# USB-NORA-W1_SCHEM_03.net
KiCad netlist of a schematic drawn in Altium Designer
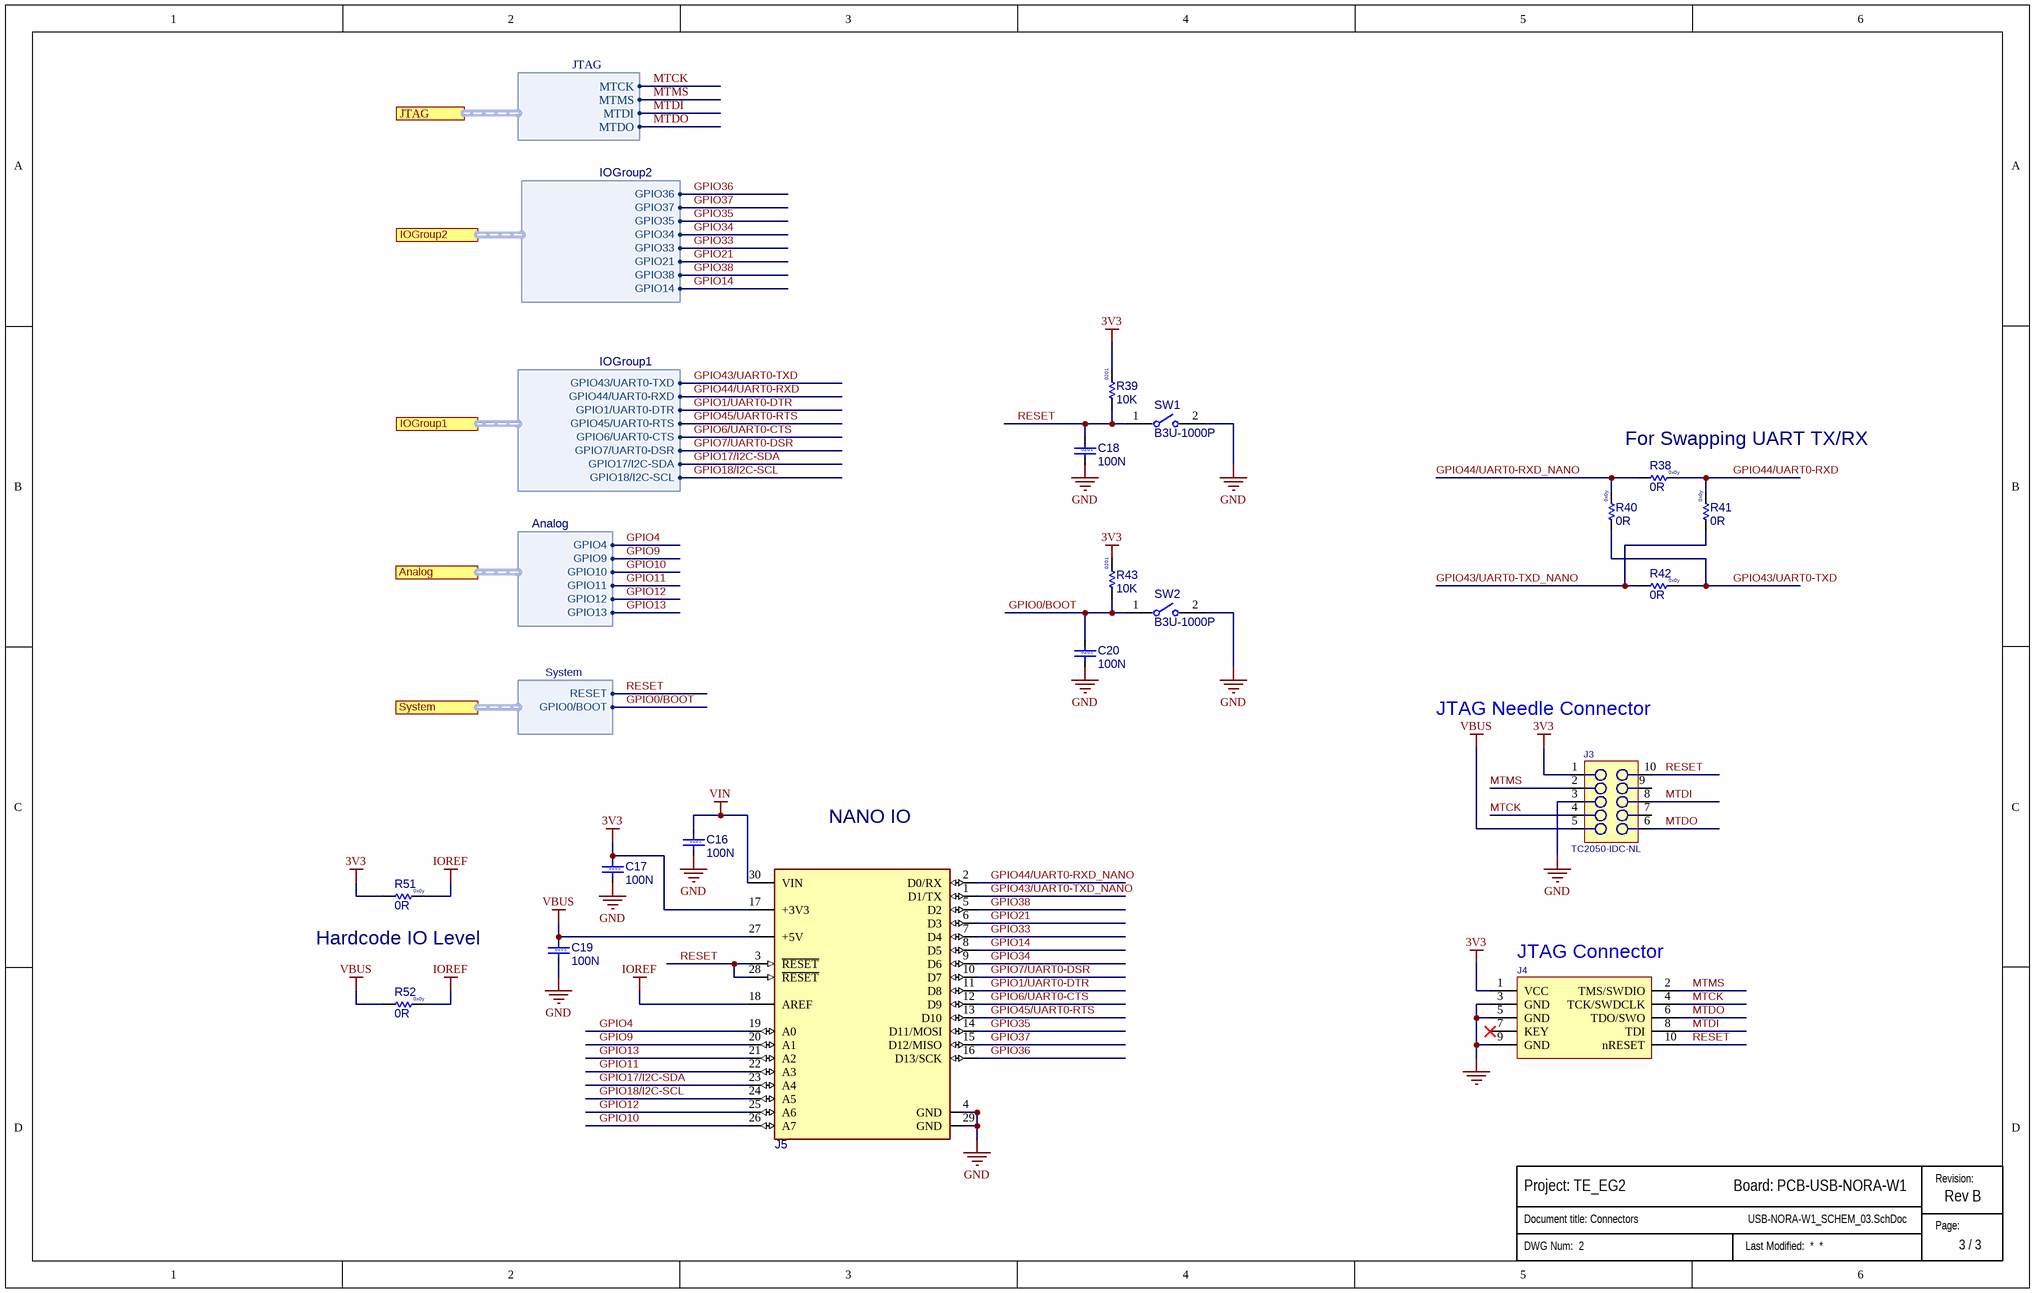
[diagram p0: USB-NORA-W1_SCHEM_03.SchDoc]

(export (version "E")
  (design (tool "Eeschema 10.0.6"))
  (components
    (comp (ref "C16")
      (value "100N")
      (footprint "Cap 0201 HD")
      (description "CAP CER X5R 0201 100N 10% 10V")
      (fields
        (field (name "SIZE") "0201")
        (field (name "PART NUMBER") "UBXH01-0000245")
        (field (name "TOLERANCE") "10%")
        (field (name "EDITOR") "dario.antonaz")
        (field (name "RELEASED BY") "jure.podmenik")
      )
      (libsource (lib "UBX_Parts_DB_Lib") (part "Cap Chip"))
    )
    (comp (ref "C17")
      (value "100N")
      (footprint "Cap 0201 HD")
      (description "CAP CER X5R 0201 100N 10% 10V")
      (fields
        (field (name "SIZE") "0201")
        (field (name "PART NUMBER") "UBXH01-0000245")
        (field (name "TOLERANCE") "10%")
        (field (name "EDITOR") "dario.antonaz")
        (field (name "RELEASED BY") "jure.podmenik")
      )
      (libsource (lib "UBX_Parts_DB_Lib") (part "Cap Chip"))
    )
    (comp (ref "C18")
      (value "100N")
      (footprint "Cap 0201 HD")
      (description "CAP CER X5R 0201 100N 10% 10V")
      (fields
        (field (name "SIZE") "0201")
        (field (name "PART NUMBER") "UBXH01-0000245")
        (field (name "TOLERANCE") "10%")
        (field (name "EDITOR") "dario.antonaz")
        (field (name "RELEASED BY") "jure.podmenik")
      )
      (libsource (lib "UBX_Parts_DB_Lib") (part "Cap Chip"))
    )
    (comp (ref "C19")
      (value "100N")
      (footprint "Cap 0201 HD")
      (description "CAP CER X5R 0201 100N 10% 10V")
      (fields
        (field (name "SIZE") "0201")
        (field (name "PART NUMBER") "UBXH01-0000245")
        (field (name "TOLERANCE") "10%")
        (field (name "EDITOR") "dario.antonaz")
        (field (name "RELEASED BY") "jure.podmenik")
      )
      (libsource (lib "UBX_Parts_DB_Lib") (part "Cap Chip"))
    )
    (comp (ref "C20")
      (value "100N")
      (footprint "Cap 0201 HD")
      (description "CAP CER X5R 0201 100N 10% 10V")
      (fields
        (field (name "SIZE") "0201")
        (field (name "PART NUMBER") "UBXH01-0000245")
        (field (name "TOLERANCE") "10%")
        (field (name "EDITOR") "dario.antonaz")
        (field (name "RELEASED BY") "jure.podmenik")
      )
      (libsource (lib "UBX_Parts_DB_Lib") (part "Cap Chip"))
    )
    (comp (ref "J3")
      (value "TC2050-IDC-NLDNP")
      (footprint "TC2050-IDC-NL")
      (description "CON PADS FOR CBL PLUG-OF-NAILS 10-PIN NO LEGS")
      (fields
        (field (name "MANUFACTURER P/N") "TC2050-IDC-NL")
        (field (name "PART NUMBER") "TC2050-IDC-NL")
        (field (name "MANUFACTURER") "TAG Connect")
        (field (name "ADDED BY") "Paul B")
      )
      (libsource (lib "LEGACY_Rigado_AltiumLib") (part "CON-10Pin_2Row_ALT"))
    )
    (comp (ref "J4")
      (value "130-00099")
      (footprint "HDR.050P-10Pin-2x5-SMT_Key")
      (description "Header 0.05\" 10Pin 2Row SMD Black")
      (fields (field (name "MANUFACTURER") "Samtec"))
      (libsource (lib "Arena_Parts_DB_Lib") (part "JTAG-10Pin"))
    )
    (comp (ref "J5")
      (value "UNK_Arduino")
      (footprint "UNK_Arduino")
      (description "ARDUINO NANO 33 IOT CONN")
      (fields (field (name "PART NUMBER") "UBXH04-0000717") (field (name "EDITOR") "aneeb.sohail"))
      (libsource (lib "UBX_Parts_DB_Lib") (part "UNK_Arduino"))
    )
    (comp (ref "R38")
      (value "0R")
      (footprint "RES 0402 HD")
      (description "RES THICK FILM CHIP 0402")
      (fields
        (field (name "SIZE") "0x0y")
        (field (name "PART NUMBER") "UBXH18-0003002")
        (field (name "TOLERANCE") "0")
        (field (name "EDITOR") "charlotte.biber")
        (field (name "RELEASED BY") "peter.mueller")
      )
      (libsource (lib "UBX_Parts_DB_Lib") (part "Res sm"))
    )
    (comp (ref "R39")
      (value "10K")
      (footprint "RES 0201 HD")
      (description "RES THICK FILM CHIP 0201 10K 5% 50mW")
      (fields
        (field (name "SIZE") "0201")
        (field (name "PART NUMBER") "UBXH18-0001097")
        (field (name "TOLERANCE") "5%")
        (field (name "EDITOR") "martin.pilik")
        (field (name "RELEASED BY") "fabrice.bret-dibat")
      )
      (libsource (lib "UBX_Parts_DB_Lib") (part "Res sm"))
    )
    (comp (ref "R40")
      (value "0R")
      (footprint "RES 0402 HD")
      (description "RES THICK FILM CHIP 0402")
      (fields
        (field (name "SIZE") "0x0y")
        (field (name "PART NUMBER") "UBXH18-0003002")
        (field (name "TOLERANCE") "0")
        (field (name "EDITOR") "charlotte.biber")
        (field (name "RELEASED BY") "peter.mueller")
      )
      (libsource (lib "UBX_Parts_DB_Lib") (part "Res sm"))
    )
    (comp (ref "R41")
      (value "0R")
      (footprint "RES 0402 HD")
      (description "RES THICK FILM CHIP 0402")
      (fields
        (field (name "SIZE") "0x0y")
        (field (name "PART NUMBER") "UBXH18-0003002")
        (field (name "TOLERANCE") "0")
        (field (name "EDITOR") "charlotte.biber")
        (field (name "RELEASED BY") "peter.mueller")
      )
      (libsource (lib "UBX_Parts_DB_Lib") (part "Res sm"))
    )
    (comp (ref "R42")
      (value "0R")
      (footprint "RES 0402 HD")
      (description "RES THICK FILM CHIP 0402")
      (fields
        (field (name "SIZE") "0x0y")
        (field (name "PART NUMBER") "UBXH18-0003002")
        (field (name "TOLERANCE") "0")
        (field (name "EDITOR") "charlotte.biber")
        (field (name "RELEASED BY") "peter.mueller")
      )
      (libsource (lib "UBX_Parts_DB_Lib") (part "Res sm"))
    )
    (comp (ref "R43")
      (value "10K")
      (footprint "RES 0201 HD")
      (description "RES THICK FILM CHIP 0201 10K 5% 50mW")
      (fields
        (field (name "SIZE") "0201")
        (field (name "PART NUMBER") "UBXH18-0001097")
        (field (name "TOLERANCE") "5%")
        (field (name "EDITOR") "martin.pilik")
        (field (name "RELEASED BY") "fabrice.bret-dibat")
      )
      (libsource (lib "UBX_Parts_DB_Lib") (part "Res sm"))
    )
    (comp (ref "R51")
      (value "0R")
      (footprint "RES 0402 HD")
      (description "RES THICK FILM CHIP 0402")
      (fields
        (field (name "SIZE") "0x0y")
        (field (name "PART NUMBER") "UBXH18-0003002")
        (field (name "TOLERANCE") "0")
        (field (name "EDITOR") "charlotte.biber")
        (field (name "RELEASED BY") "peter.mueller")
      )
      (libsource (lib "UBX_Parts_DB_Lib") (part "Res sm"))
    )
    (comp (ref "R52")
      (value "0R")
      (footprint "RES 0402 HD")
      (description "RES THICK FILM CHIP 0402")
      (fields
        (field (name "SIZE") "0x0y")
        (field (name "PART NUMBER") "UBXH18-0003002")
        (field (name "TOLERANCE") "0")
        (field (name "EDITOR") "charlotte.biber")
        (field (name "RELEASED BY") "peter.mueller")
      )
      (libsource (lib "UBX_Parts_DB_Lib") (part "Res sm"))
    )
    (comp (ref "SW1")
      (value "B3U-1000P")
      (footprint "FP-B3U-1000P-MFG")
      (description "SWITCH TACTILE SPST-NO 0.05A 12V")
      (libsource (lib "Altium Content Vault") (part "ae622034201233ca1abcedc05908f33"))
    )
    (comp (ref "SW2")
      (value "B3U-1000P")
      (footprint "FP-B3U-1000P-MFG")
      (description "SWITCH TACTILE SPST-NO 0.05A 12V")
      (libsource (lib "Altium Content Vault") (part "ae622034201233ca1abcedc05908f33"))
    )
  )
  (nets
    (net (code "6") (name "/GPIO0{slash}BOOT") (class "Default")
      (node (ref "C20") (pin "1") (pinfunction "1_1") (pintype "passive"))
      (node (ref "R43") (pin "1") (pinfunction "1_1") (pintype "passive"))
      (node (ref "SW2") (pin "1") (pinfunction "1_1") (pintype "passive"))
    )
    (net (code "7") (name "/GPIO1{slash}UART0-DTR") (class "Default")
      (node (ref "J5") (pin "11") (pinfunction "D8_11") (pintype "bidirectional"))
    )
    (net (code "8") (name "/GPIO4") (class "Default")
      (node (ref "J5") (pin "19") (pinfunction "A0_19") (pintype "bidirectional"))
    )
    (net (code "9") (name "/GPIO6{slash}UART0-CTS") (class "Default")
      (node (ref "J5") (pin "12") (pinfunction "D9_12") (pintype "bidirectional"))
    )
    (net (code "10") (name "/GPIO7{slash}UART0-DSR") (class "Default")
      (node (ref "J5") (pin "10") (pinfunction "D7_10") (pintype "bidirectional"))
    )
    (net (code "11") (name "/GPIO9") (class "Default")
      (node (ref "J5") (pin "20") (pinfunction "A1_20") (pintype "bidirectional"))
    )
    (net (code "12") (name "/GPIO10") (class "Default")
      (node (ref "J5") (pin "26") (pinfunction "A7_26") (pintype "bidirectional"))
    )
    (net (code "13") (name "/GPIO11") (class "Default")
      (node (ref "J5") (pin "22") (pinfunction "A3_22") (pintype "bidirectional"))
    )
    (net (code "14") (name "/GPIO12") (class "Default")
      (node (ref "J5") (pin "25") (pinfunction "A6_25") (pintype "bidirectional"))
    )
    (net (code "15") (name "/GPIO13") (class "Default")
      (node (ref "J5") (pin "21") (pinfunction "A2_21") (pintype "bidirectional"))
    )
    (net (code "16") (name "/GPIO14") (class "Default")
      (node (ref "J5") (pin "8") (pinfunction "D5_8") (pintype "bidirectional"))
    )
    (net (code "17") (name "/GPIO17{slash}I2C-SDA") (class "Default")
      (node (ref "J5") (pin "23") (pinfunction "A4_23") (pintype "bidirectional"))
    )
    (net (code "18") (name "/GPIO18{slash}I2C-SCL") (class "Default")
      (node (ref "J5") (pin "24") (pinfunction "A5_24") (pintype "bidirectional"))
    )
    (net (code "19") (name "/GPIO21") (class "Default")
      (node (ref "J5") (pin "6") (pinfunction "D3_6") (pintype "bidirectional"))
    )
    (net (code "20") (name "/GPIO33") (class "Default")
      (node (ref "J5") (pin "7") (pinfunction "D4_7") (pintype "bidirectional"))
    )
    (net (code "21") (name "/GPIO34") (class "Default")
      (node (ref "J5") (pin "9") (pinfunction "D6_9") (pintype "bidirectional"))
    )
    (net (code "22") (name "/GPIO35") (class "Default")
      (node (ref "J5") (pin "14") (pinfunction "D11/MOSI_14") (pintype "bidirectional"))
    )
    (net (code "23") (name "/GPIO36") (class "Default")
      (node (ref "J5") (pin "16") (pinfunction "D13/SCK_16") (pintype "bidirectional"))
    )
    (net (code "24") (name "/GPIO37") (class "Default")
      (node (ref "J5") (pin "15") (pinfunction "D12/MISO_15") (pintype "bidirectional"))
    )
    (net (code "25") (name "/GPIO38") (class "Default")
      (node (ref "J5") (pin "5") (pinfunction "D2_5") (pintype "bidirectional"))
    )
    (net (code "26") (name "/GPIO43{slash}UART0-TXD") (class "Default")
      (node (ref "R40") (pin "1") (pinfunction "1_1") (pintype "passive"))
      (node (ref "R42") (pin "2") (pinfunction "2_2") (pintype "passive"))
    )
    (net (code "27") (name "/GPIO43{slash}UART0-TXD_NANO") (class "Default")
      (node (ref "J5") (pin "1") (pinfunction "D1/TX_1") (pintype "bidirectional"))
      (node (ref "R41") (pin "1") (pinfunction "1_1") (pintype "passive"))
      (node (ref "R42") (pin "1") (pinfunction "1_1") (pintype "passive"))
    )
    (net (code "28") (name "/GPIO44{slash}UART0-RXD") (class "Default")
      (node (ref "R38") (pin "2") (pinfunction "2_2") (pintype "passive"))
      (node (ref "R41") (pin "2") (pinfunction "2_2") (pintype "passive"))
    )
    (net (code "29") (name "/GPIO44{slash}UART0-RXD_NANO") (class "Default")
      (node (ref "J5") (pin "2") (pinfunction "D0/RX_2") (pintype "bidirectional"))
      (node (ref "R38") (pin "1") (pinfunction "1_1") (pintype "passive"))
      (node (ref "R40") (pin "2") (pinfunction "2_2") (pintype "passive"))
    )
    (net (code "30") (name "/GPIO45{slash}UART0-RTS") (class "Default")
      (node (ref "J5") (pin "13") (pinfunction "D10_13") (pintype "bidirectional"))
    )
    (net (code "31") (name "/MTCK") (class "Default")
      (node (ref "J3") (pin "4") (pintype "passive"))
      (node (ref "J4") (pin "4") (pinfunction "TCK/SWDCLK_4") (pintype "passive"))
    )
    (net (code "32") (name "/MTDI") (class "Default")
      (node (ref "J3") (pin "8") (pintype "passive"))
      (node (ref "J4") (pin "8") (pinfunction "TDI_8") (pintype "passive"))
    )
    (net (code "33") (name "/MTDO") (class "Default")
      (node (ref "J3") (pin "6") (pintype "passive"))
      (node (ref "J4") (pin "6") (pinfunction "TDO/SWO_6") (pintype "passive"))
    )
    (net (code "34") (name "/MTMS") (class "Default")
      (node (ref "J3") (pin "2") (pintype "passive"))
      (node (ref "J4") (pin "2") (pinfunction "TMS/SWDIO_2") (pintype "passive"))
    )
    (net (code "35") (name "/RESET") (class "Default")
      (node (ref "C18") (pin "1") (pinfunction "1_1") (pintype "passive"))
      (node (ref "J3") (pin "10") (pintype "passive"))
      (node (ref "J4") (pin "10") (pinfunction "nRESET_10") (pintype "passive"))
      (node (ref "J5") (pin "28") (pinfunction "~{RESET}_28") (pintype "input"))
      (node (ref "J5") (pin "3") (pinfunction "~{RESET}_3") (pintype "input"))
      (node (ref "R39") (pin "1") (pinfunction "1_1") (pintype "passive"))
      (node (ref "SW1") (pin "1") (pinfunction "1_1") (pintype "passive"))
    )
    (net (code "41") (name "3V3") (class "Default")
      (node (ref "C17") (pin "1") (pinfunction "1_1") (pintype "passive"))
      (node (ref "J3") (pin "1") (pintype "passive"))
      (node (ref "J4") (pin "1") (pinfunction "VCC_1") (pintype "passive"))
      (node (ref "J5") (pin "17") (pinfunction "+3V3_17") (pintype "power_in"))
      (node (ref "R39") (pin "2") (pinfunction "2_2") (pintype "passive"))
      (node (ref "R43") (pin "2") (pinfunction "2_2") (pintype "passive"))
      (node (ref "R51") (pin "1") (pinfunction "1_1") (pintype "passive"))
    )
    (net (code "42") (name "GND") (class "Default")
      (node (ref "C16") (pin "2") (pinfunction "2_2") (pintype "passive"))
      (node (ref "C17") (pin "2") (pinfunction "2_2") (pintype "passive"))
      (node (ref "C18") (pin "2") (pinfunction "2_2") (pintype "passive"))
      (node (ref "C19") (pin "2") (pinfunction "2_2") (pintype "passive"))
      (node (ref "C20") (pin "2") (pinfunction "2_2") (pintype "passive"))
      (node (ref "J3") (pin "3") (pintype "passive"))
      (node (ref "J4") (pin "3") (pinfunction "GND_3") (pintype "passive"))
      (node (ref "J4") (pin "5") (pinfunction "GND_5") (pintype "passive"))
      (node (ref "J4") (pin "9") (pinfunction "GND_9") (pintype "passive"))
      (node (ref "J5") (pin "29") (pinfunction "GND_29") (pintype "power_in"))
      (node (ref "J5") (pin "4") (pinfunction "GND_4") (pintype "power_in"))
      (node (ref "SW1") (pin "2") (pinfunction "2_2") (pintype "passive"))
      (node (ref "SW2") (pin "2") (pinfunction "2_2") (pintype "passive"))
    )
    (net (code "43") (name "IOREF") (class "Default")
      (node (ref "J5") (pin "18") (pinfunction "AREF_18") (pintype "passive"))
      (node (ref "R51") (pin "2") (pinfunction "2_2") (pintype "passive"))
      (node (ref "R52") (pin "2") (pinfunction "2_2") (pintype "passive"))
    )
    (net (code "44") (name "VBUS") (class "Default")
      (node (ref "C19") (pin "1") (pinfunction "1_1") (pintype "passive"))
      (node (ref "J3") (pin "5") (pintype "passive"))
      (node (ref "J5") (pin "27") (pinfunction "+5V_27") (pintype "power_in"))
      (node (ref "R52") (pin "1") (pinfunction "1_1") (pintype "passive"))
    )
    (net (code "45") (name "VIN") (class "Default")
      (node (ref "C16") (pin "1") (pinfunction "1_1") (pintype "passive"))
      (node (ref "J5") (pin "30") (pinfunction "VIN_30") (pintype "power_in"))
    )
    (net (code "46") (name "unconnected-(J3-Pad7)") (class "Default")
      (node (ref "J3") (pin "7") (pintype "passive"))
    )
    (net (code "47") (name "unconnected-(J3-Pad9)") (class "Default")
      (node (ref "J3") (pin "9") (pintype "passive"))
    )
    (net (code "48") (name "unconnected-(J4-KEY-Pad7)") (class "Default")
      (node (ref "J4") (pin "7") (pinfunction "KEY_7") (pintype "passive+no_connect"))
    )
  )
)
